# PLT-01-RevC.net
KiCad netlist of a schematic drawn in EAGLE
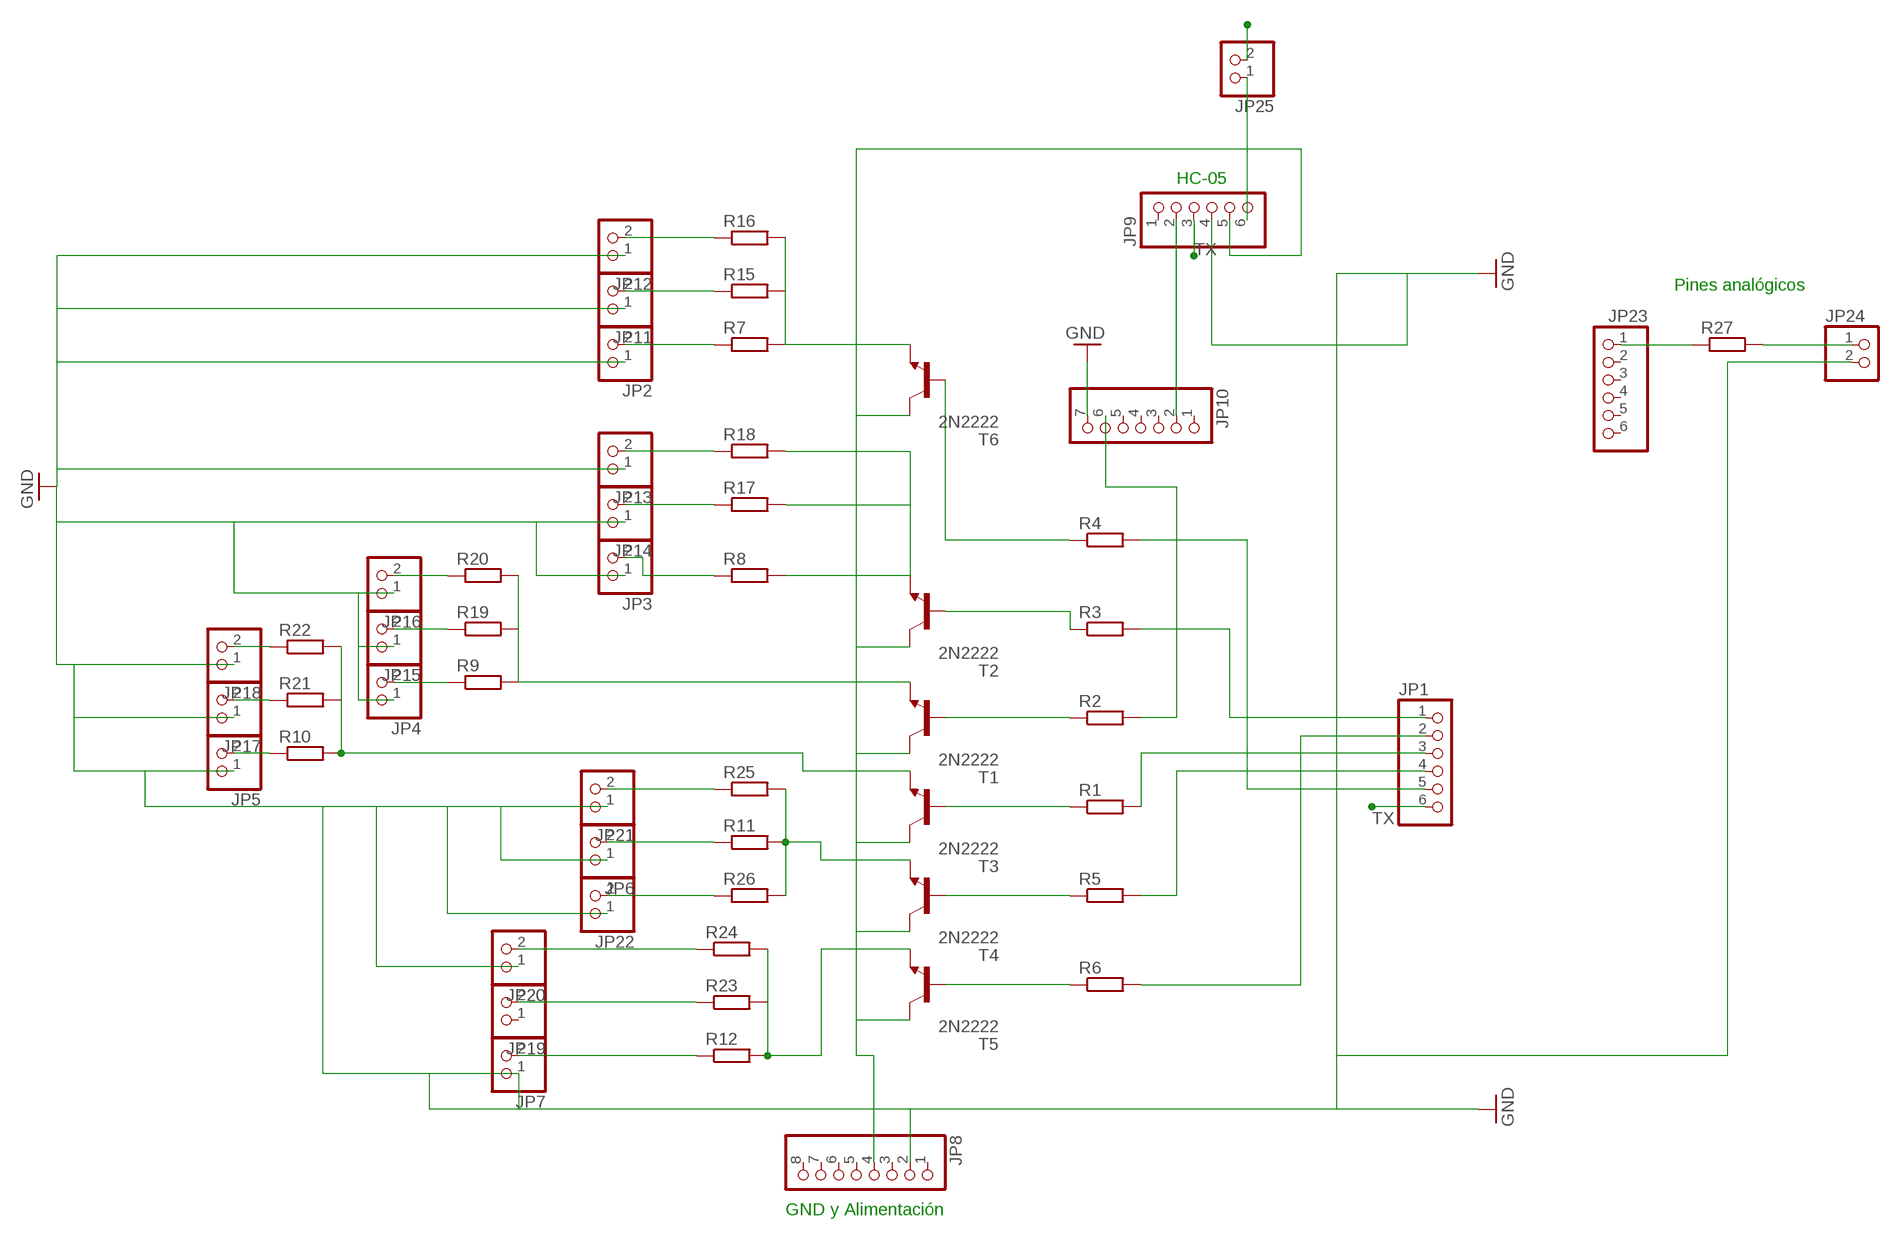
[diagram p0: schematic, sheet 1]

(export (version "E")
  (design (tool "Eeschema 10.0.6"))
  (components
    (comp (ref "JP1")
      (value "PINHD-1X6")
      (footprint "eagle-import:1X06")
      (libsource (lib "eagle-import") (part "PINHD-1X6"))
    )
    (comp (ref "JP2")
      (value "PINHD-1X2")
      (footprint "eagle-import:1X02")
      (libsource (lib "eagle-import") (part "PINHD-1X2"))
    )
    (comp (ref "JP3")
      (value "PINHD-1X2")
      (footprint "eagle-import:1X02")
      (libsource (lib "eagle-import") (part "PINHD-1X2"))
    )
    (comp (ref "JP4")
      (value "PINHD-1X2")
      (footprint "eagle-import:1X02")
      (libsource (lib "eagle-import") (part "PINHD-1X2"))
    )
    (comp (ref "JP5")
      (value "PINHD-1X2")
      (footprint "eagle-import:1X02")
      (libsource (lib "eagle-import") (part "PINHD-1X2"))
    )
    (comp (ref "JP6")
      (value "PINHD-1X2")
      (footprint "eagle-import:1X02")
      (libsource (lib "eagle-import") (part "PINHD-1X2"))
    )
    (comp (ref "JP7")
      (value "PINHD-1X2")
      (footprint "eagle-import:1X02")
      (libsource (lib "eagle-import") (part "PINHD-1X2"))
    )
    (comp (ref "JP8")
      (value "PINHD-1X8")
      (footprint "eagle-import:1X08")
      (libsource (lib "eagle-import") (part "PINHD-1X8"))
    )
    (comp (ref "JP9")
      (value "PINHD-1X6")
      (footprint "eagle-import:1X06")
      (libsource (lib "eagle-import") (part "PINHD-1X6"))
    )
    (comp (ref "JP10")
      (value "PINHD-1X7")
      (footprint "eagle-import:1X07")
      (libsource (lib "eagle-import") (part "PINHD-1X7"))
    )
    (comp (ref "JP11")
      (value "PINHD-1X2")
      (footprint "eagle-import:1X02")
      (libsource (lib "eagle-import") (part "PINHD-1X2"))
    )
    (comp (ref "JP12")
      (value "PINHD-1X2")
      (footprint "eagle-import:1X02")
      (libsource (lib "eagle-import") (part "PINHD-1X2"))
    )
    (comp (ref "JP13")
      (value "PINHD-1X2")
      (footprint "eagle-import:1X02")
      (libsource (lib "eagle-import") (part "PINHD-1X2"))
    )
    (comp (ref "JP14")
      (value "PINHD-1X2")
      (footprint "eagle-import:1X02")
      (libsource (lib "eagle-import") (part "PINHD-1X2"))
    )
    (comp (ref "JP15")
      (value "PINHD-1X2")
      (footprint "eagle-import:1X02")
      (libsource (lib "eagle-import") (part "PINHD-1X2"))
    )
    (comp (ref "JP16")
      (value "PINHD-1X2")
      (footprint "eagle-import:1X02")
      (libsource (lib "eagle-import") (part "PINHD-1X2"))
    )
    (comp (ref "JP17")
      (value "PINHD-1X2")
      (footprint "eagle-import:1X02")
      (libsource (lib "eagle-import") (part "PINHD-1X2"))
    )
    (comp (ref "JP18")
      (value "PINHD-1X2")
      (footprint "eagle-import:1X02")
      (libsource (lib "eagle-import") (part "PINHD-1X2"))
    )
    (comp (ref "JP19")
      (value "PINHD-1X2")
      (footprint "eagle-import:1X02")
      (libsource (lib "eagle-import") (part "PINHD-1X2"))
    )
    (comp (ref "JP20")
      (value "PINHD-1X2")
      (footprint "eagle-import:1X02")
      (libsource (lib "eagle-import") (part "PINHD-1X2"))
    )
    (comp (ref "JP21")
      (value "PINHD-1X2")
      (footprint "eagle-import:1X02")
      (libsource (lib "eagle-import") (part "PINHD-1X2"))
    )
    (comp (ref "JP22")
      (value "PINHD-1X2")
      (footprint "eagle-import:1X02")
      (libsource (lib "eagle-import") (part "PINHD-1X2"))
    )
    (comp (ref "JP23")
      (value "PINHD-1X6")
      (footprint "eagle-import:1X06")
      (libsource (lib "eagle-import") (part "PINHD-1X6"))
    )
    (comp (ref "JP24")
      (value "PINHD-1X2")
      (footprint "eagle-import:1X02")
      (libsource (lib "eagle-import") (part "PINHD-1X2"))
    )
    (comp (ref "JP25")
      (value "PINHD-1X2")
      (footprint "eagle-import:1X02")
      (libsource (lib "eagle-import") (part "PINHD-1X2"))
    )
    (comp (ref "R1")
      (value "R-EU_0207/10")
      (footprint "eagle-import:0207_10")
      (libsource (lib "eagle-import") (part "R-EU_0207/10"))
    )
    (comp (ref "R2")
      (value "R-EU_0207/10")
      (footprint "eagle-import:0207_10")
      (libsource (lib "eagle-import") (part "R-EU_0207/10"))
    )
    (comp (ref "R3")
      (value "R-EU_0207/10")
      (footprint "eagle-import:0207_10")
      (libsource (lib "eagle-import") (part "R-EU_0207/10"))
    )
    (comp (ref "R4")
      (value "R-EU_0207/10")
      (footprint "eagle-import:0207_10")
      (libsource (lib "eagle-import") (part "R-EU_0207/10"))
    )
    (comp (ref "R5")
      (value "R-EU_0207/10")
      (footprint "eagle-import:0207_10")
      (libsource (lib "eagle-import") (part "R-EU_0207/10"))
    )
    (comp (ref "R6")
      (value "R-EU_0207/10")
      (footprint "eagle-import:0207_10")
      (libsource (lib "eagle-import") (part "R-EU_0207/10"))
    )
    (comp (ref "R7")
      (value "R-EU_0207/10")
      (footprint "eagle-import:0207_10")
      (libsource (lib "eagle-import") (part "R-EU_0207/10"))
    )
    (comp (ref "R8")
      (value "R-EU_0207/10")
      (footprint "eagle-import:0207_10")
      (libsource (lib "eagle-import") (part "R-EU_0207/10"))
    )
    (comp (ref "R9")
      (value "R-EU_0207/10")
      (footprint "eagle-import:0207_10")
      (libsource (lib "eagle-import") (part "R-EU_0207/10"))
    )
    (comp (ref "R10")
      (value "R-EU_0207/10")
      (footprint "eagle-import:0207_10")
      (libsource (lib "eagle-import") (part "R-EU_0207/10"))
    )
    (comp (ref "R11")
      (value "R-EU_0207/10")
      (footprint "eagle-import:0207_10")
      (libsource (lib "eagle-import") (part "R-EU_0207/10"))
    )
    (comp (ref "R12")
      (value "R-EU_0207/10")
      (footprint "eagle-import:0207_10")
      (libsource (lib "eagle-import") (part "R-EU_0207/10"))
    )
    (comp (ref "R15")
      (value "R-EU_0207/10")
      (footprint "eagle-import:0207_10")
      (libsource (lib "eagle-import") (part "R-EU_0207/10"))
    )
    (comp (ref "R16")
      (value "R-EU_0207/10")
      (footprint "eagle-import:0207_10")
      (libsource (lib "eagle-import") (part "R-EU_0207/10"))
    )
    (comp (ref "R17")
      (value "R-EU_0207/10")
      (footprint "eagle-import:0207_10")
      (libsource (lib "eagle-import") (part "R-EU_0207/10"))
    )
    (comp (ref "R18")
      (value "R-EU_0207/10")
      (footprint "eagle-import:0207_10")
      (libsource (lib "eagle-import") (part "R-EU_0207/10"))
    )
    (comp (ref "R19")
      (value "R-EU_0207/10")
      (footprint "eagle-import:0207_10")
      (libsource (lib "eagle-import") (part "R-EU_0207/10"))
    )
    (comp (ref "R20")
      (value "R-EU_0207/10")
      (footprint "eagle-import:0207_10")
      (libsource (lib "eagle-import") (part "R-EU_0207/10"))
    )
    (comp (ref "R21")
      (value "R-EU_0207/10")
      (footprint "eagle-import:0207_10")
      (libsource (lib "eagle-import") (part "R-EU_0207/10"))
    )
    (comp (ref "R22")
      (value "R-EU_0207/10")
      (footprint "eagle-import:0207_10")
      (libsource (lib "eagle-import") (part "R-EU_0207/10"))
    )
    (comp (ref "R23")
      (value "R-EU_0207/10")
      (footprint "eagle-import:0207_10")
      (libsource (lib "eagle-import") (part "R-EU_0207/10"))
    )
    (comp (ref "R24")
      (value "R-EU_0207/10")
      (footprint "eagle-import:0207_10")
      (libsource (lib "eagle-import") (part "R-EU_0207/10"))
    )
    (comp (ref "R25")
      (value "R-EU_0207/10")
      (footprint "eagle-import:0207_10")
      (libsource (lib "eagle-import") (part "R-EU_0207/10"))
    )
    (comp (ref "R26")
      (value "R-EU_0207/10")
      (footprint "eagle-import:0207_10")
      (libsource (lib "eagle-import") (part "R-EU_0207/10"))
    )
    (comp (ref "R27")
      (value "R-EU_0207/10")
      (footprint "eagle-import:0207_10")
      (libsource (lib "eagle-import") (part "R-EU_0207/10"))
    )
    (comp (ref "T1")
      (value "2N2222")
      (footprint "eagle-import:TO92-EBC-OVAL")
      (libsource (lib "eagle-import") (part "2N2222"))
    )
    (comp (ref "T2")
      (value "2N2222")
      (footprint "eagle-import:TO92-EBC-OVAL")
      (libsource (lib "eagle-import") (part "2N2222"))
    )
    (comp (ref "T3")
      (value "2N2222")
      (footprint "eagle-import:TO92-EBC-OVAL")
      (libsource (lib "eagle-import") (part "2N2222"))
    )
    (comp (ref "T4")
      (value "2N2222")
      (footprint "eagle-import:TO92-EBC-OVAL")
      (libsource (lib "eagle-import") (part "2N2222"))
    )
    (comp (ref "T5")
      (value "2N2222")
      (footprint "eagle-import:TO92-EBC-OVAL")
      (libsource (lib "eagle-import") (part "2N2222"))
    )
    (comp (ref "T6")
      (value "2N2222")
      (footprint "eagle-import:TO92-EBC-OVAL")
      (libsource (lib "eagle-import") (part "2N2222"))
    )
  )
  (nets
    (net (code "1") (name "/5V") (class "Default")
      (node (ref "JP25") (pin "2") (pinfunction "2_2") (pintype "passive"))
      (node (ref "JP8") (pin "4") (pinfunction "4_4") (pintype "passive"))
      (node (ref "JP9") (pin "5") (pinfunction "5_5") (pintype "passive"))
      (node (ref "T1") (pin "C") (pinfunction "C_C") (pintype "passive"))
      (node (ref "T2") (pin "C") (pinfunction "C_C") (pintype "passive"))
      (node (ref "T3") (pin "C") (pinfunction "C_C") (pintype "passive"))
      (node (ref "T4") (pin "C") (pinfunction "C_C") (pintype "passive"))
      (node (ref "T5") (pin "C") (pinfunction "C_C") (pintype "passive"))
      (node (ref "T6") (pin "C") (pinfunction "C_C") (pintype "passive"))
    )
    (net (code "2") (name "/TX") (class "Default")
      (node (ref "JP1") (pin "6") (pinfunction "6_6") (pintype "passive"))
      (node (ref "JP9") (pin "3") (pinfunction "3_3") (pintype "passive"))
    )
    (net (code "3") (name "GND") (class "Default")
      (node (ref "JP10") (pin "7") (pinfunction "7_7") (pintype "passive"))
      (node (ref "JP11") (pin "1") (pinfunction "1_1") (pintype "passive"))
      (node (ref "JP12") (pin "1") (pinfunction "1_1") (pintype "passive"))
      (node (ref "JP13") (pin "1") (pinfunction "1_1") (pintype "passive"))
      (node (ref "JP14") (pin "1") (pinfunction "1_1") (pintype "passive"))
      (node (ref "JP15") (pin "1") (pinfunction "1_1") (pintype "passive"))
      (node (ref "JP16") (pin "1") (pinfunction "1_1") (pintype "passive"))
      (node (ref "JP17") (pin "1") (pinfunction "1_1") (pintype "passive"))
      (node (ref "JP18") (pin "1") (pinfunction "1_1") (pintype "passive"))
      (node (ref "JP2") (pin "1") (pinfunction "1_1") (pintype "passive"))
      (node (ref "JP20") (pin "1") (pinfunction "1_1") (pintype "passive"))
      (node (ref "JP21") (pin "1") (pinfunction "1_1") (pintype "passive"))
      (node (ref "JP22") (pin "1") (pinfunction "1_1") (pintype "passive"))
      (node (ref "JP24") (pin "2") (pinfunction "2_2") (pintype "passive"))
      (node (ref "JP3") (pin "1") (pinfunction "1_1") (pintype "passive"))
      (node (ref "JP4") (pin "1") (pinfunction "1_1") (pintype "passive"))
      (node (ref "JP5") (pin "1") (pinfunction "1_1") (pintype "passive"))
      (node (ref "JP6") (pin "1") (pinfunction "1_1") (pintype "passive"))
      (node (ref "JP7") (pin "1") (pinfunction "1_1") (pintype "passive"))
      (node (ref "JP8") (pin "2") (pinfunction "2_2") (pintype "passive"))
      (node (ref "JP9") (pin "4") (pinfunction "4_4") (pintype "passive"))
    )
    (net (code "4") (name "Net-(JP1-Pad1)") (class "Default")
      (node (ref "JP1") (pin "1") (pinfunction "1_1") (pintype "passive"))
      (node (ref "R3") (pin "2") (pinfunction "2_2") (pintype "passive"))
    )
    (net (code "5") (name "Net-(JP1-Pad2)") (class "Default")
      (node (ref "JP1") (pin "2") (pinfunction "2_2") (pintype "passive"))
      (node (ref "R6") (pin "2") (pinfunction "2_2") (pintype "passive"))
    )
    (net (code "6") (name "Net-(JP1-Pad3)") (class "Default")
      (node (ref "JP1") (pin "3") (pinfunction "3_3") (pintype "passive"))
      (node (ref "R1") (pin "2") (pinfunction "2_2") (pintype "passive"))
    )
    (net (code "7") (name "Net-(JP1-Pad4)") (class "Default")
      (node (ref "JP1") (pin "4") (pinfunction "4_4") (pintype "passive"))
      (node (ref "R5") (pin "2") (pinfunction "2_2") (pintype "passive"))
    )
    (net (code "8") (name "Net-(JP1-Pad5)") (class "Default")
      (node (ref "JP1") (pin "5") (pinfunction "5_5") (pintype "passive"))
      (node (ref "R4") (pin "2") (pinfunction "2_2") (pintype "passive"))
    )
    (net (code "9") (name "Net-(JP2-Pad2)") (class "Default")
      (node (ref "JP2") (pin "2") (pinfunction "2_2") (pintype "passive"))
      (node (ref "R7") (pin "1") (pinfunction "1_1") (pintype "passive"))
    )
    (net (code "10") (name "Net-(JP3-Pad2)") (class "Default")
      (node (ref "JP3") (pin "2") (pinfunction "2_2") (pintype "passive"))
      (node (ref "R8") (pin "1") (pinfunction "1_1") (pintype "passive"))
    )
    (net (code "11") (name "Net-(JP4-Pad2)") (class "Default")
      (node (ref "JP4") (pin "2") (pinfunction "2_2") (pintype "passive"))
      (node (ref "R9") (pin "1") (pinfunction "1_1") (pintype "passive"))
    )
    (net (code "12") (name "Net-(JP5-Pad2)") (class "Default")
      (node (ref "JP5") (pin "2") (pinfunction "2_2") (pintype "passive"))
      (node (ref "R10") (pin "1") (pinfunction "1_1") (pintype "passive"))
    )
    (net (code "13") (name "Net-(JP6-Pad2)") (class "Default")
      (node (ref "JP6") (pin "2") (pinfunction "2_2") (pintype "passive"))
      (node (ref "R11") (pin "1") (pinfunction "1_1") (pintype "passive"))
    )
    (net (code "14") (name "Net-(JP7-Pad2)") (class "Default")
      (node (ref "JP7") (pin "2") (pinfunction "2_2") (pintype "passive"))
      (node (ref "R12") (pin "1") (pinfunction "1_1") (pintype "passive"))
    )
    (net (code "15") (name "Net-(JP10-Pad2)") (class "Default")
      (node (ref "JP10") (pin "2") (pinfunction "2_2") (pintype "passive"))
      (node (ref "JP9") (pin "2") (pinfunction "2_2") (pintype "passive"))
    )
    (net (code "16") (name "Net-(JP10-Pad6)") (class "Default")
      (node (ref "JP10") (pin "6") (pinfunction "6_6") (pintype "passive"))
      (node (ref "R2") (pin "2") (pinfunction "2_2") (pintype "passive"))
    )
    (net (code "17") (name "Net-(JP11-Pad2)") (class "Default")
      (node (ref "JP11") (pin "2") (pinfunction "2_2") (pintype "passive"))
      (node (ref "R15") (pin "1") (pinfunction "1_1") (pintype "passive"))
    )
    (net (code "18") (name "Net-(JP12-Pad2)") (class "Default")
      (node (ref "JP12") (pin "2") (pinfunction "2_2") (pintype "passive"))
      (node (ref "R16") (pin "1") (pinfunction "1_1") (pintype "passive"))
    )
    (net (code "19") (name "Net-(JP13-Pad2)") (class "Default")
      (node (ref "JP13") (pin "2") (pinfunction "2_2") (pintype "passive"))
      (node (ref "R18") (pin "1") (pinfunction "1_1") (pintype "passive"))
    )
    (net (code "20") (name "Net-(JP14-Pad2)") (class "Default")
      (node (ref "JP14") (pin "2") (pinfunction "2_2") (pintype "passive"))
      (node (ref "R17") (pin "1") (pinfunction "1_1") (pintype "passive"))
    )
    (net (code "21") (name "Net-(JP15-Pad2)") (class "Default")
      (node (ref "JP15") (pin "2") (pinfunction "2_2") (pintype "passive"))
      (node (ref "R19") (pin "1") (pinfunction "1_1") (pintype "passive"))
    )
    (net (code "22") (name "Net-(JP16-Pad2)") (class "Default")
      (node (ref "JP16") (pin "2") (pinfunction "2_2") (pintype "passive"))
      (node (ref "R20") (pin "1") (pinfunction "1_1") (pintype "passive"))
    )
    (net (code "23") (name "Net-(JP17-Pad2)") (class "Default")
      (node (ref "JP17") (pin "2") (pinfunction "2_2") (pintype "passive"))
      (node (ref "R21") (pin "1") (pinfunction "1_1") (pintype "passive"))
    )
    (net (code "24") (name "Net-(JP18-Pad2)") (class "Default")
      (node (ref "JP18") (pin "2") (pinfunction "2_2") (pintype "passive"))
      (node (ref "R22") (pin "1") (pinfunction "1_1") (pintype "passive"))
    )
    (net (code "25") (name "Net-(JP19-Pad2)") (class "Default")
      (node (ref "JP19") (pin "2") (pinfunction "2_2") (pintype "passive"))
      (node (ref "R23") (pin "1") (pinfunction "1_1") (pintype "passive"))
    )
    (net (code "26") (name "Net-(JP20-Pad2)") (class "Default")
      (node (ref "JP20") (pin "2") (pinfunction "2_2") (pintype "passive"))
      (node (ref "R24") (pin "1") (pinfunction "1_1") (pintype "passive"))
    )
    (net (code "27") (name "Net-(JP21-Pad2)") (class "Default")
      (node (ref "JP21") (pin "2") (pinfunction "2_2") (pintype "passive"))
      (node (ref "R25") (pin "1") (pinfunction "1_1") (pintype "passive"))
    )
    (net (code "28") (name "Net-(JP22-Pad2)") (class "Default")
      (node (ref "JP22") (pin "2") (pinfunction "2_2") (pintype "passive"))
      (node (ref "R26") (pin "1") (pinfunction "1_1") (pintype "passive"))
    )
    (net (code "29") (name "Net-(JP23-Pad1)") (class "Default")
      (node (ref "JP23") (pin "1") (pinfunction "1_1") (pintype "passive"))
      (node (ref "R27") (pin "1") (pinfunction "1_1") (pintype "passive"))
    )
    (net (code "30") (name "Net-(JP24-Pad1)") (class "Default")
      (node (ref "JP24") (pin "1") (pinfunction "1_1") (pintype "passive"))
      (node (ref "R27") (pin "2") (pinfunction "2_2") (pintype "passive"))
    )
    (net (code "31") (name "Net-(JP25-Pad1)") (class "Default")
      (node (ref "JP25") (pin "1") (pinfunction "1_1") (pintype "passive"))
      (node (ref "JP9") (pin "6") (pinfunction "6_6") (pintype "passive"))
    )
    (net (code "32") (name "Net-(R1-Pad1)") (class "Default")
      (node (ref "R1") (pin "1") (pinfunction "1_1") (pintype "passive"))
      (node (ref "T3") (pin "B") (pinfunction "B_B") (pintype "passive"))
    )
    (net (code "33") (name "Net-(R2-Pad1)") (class "Default")
      (node (ref "R2") (pin "1") (pinfunction "1_1") (pintype "passive"))
      (node (ref "T1") (pin "B") (pinfunction "B_B") (pintype "passive"))
    )
    (net (code "34") (name "Net-(R3-Pad1)") (class "Default")
      (node (ref "R3") (pin "1") (pinfunction "1_1") (pintype "passive"))
      (node (ref "T2") (pin "B") (pinfunction "B_B") (pintype "passive"))
    )
    (net (code "35") (name "Net-(R4-Pad1)") (class "Default")
      (node (ref "R4") (pin "1") (pinfunction "1_1") (pintype "passive"))
      (node (ref "T6") (pin "B") (pinfunction "B_B") (pintype "passive"))
    )
    (net (code "36") (name "Net-(R5-Pad1)") (class "Default")
      (node (ref "R5") (pin "1") (pinfunction "1_1") (pintype "passive"))
      (node (ref "T4") (pin "B") (pinfunction "B_B") (pintype "passive"))
    )
    (net (code "37") (name "Net-(R6-Pad1)") (class "Default")
      (node (ref "R6") (pin "1") (pinfunction "1_1") (pintype "passive"))
      (node (ref "T5") (pin "B") (pinfunction "B_B") (pintype "passive"))
    )
    (net (code "38") (name "Net-(R10-Pad2)") (class "Default")
      (node (ref "R10") (pin "2") (pinfunction "2_2") (pintype "passive"))
      (node (ref "R21") (pin "2") (pinfunction "2_2") (pintype "passive"))
      (node (ref "R22") (pin "2") (pinfunction "2_2") (pintype "passive"))
      (node (ref "T3") (pin "E") (pinfunction "E_E") (pintype "passive"))
    )
    (net (code "39") (name "Net-(R11-Pad2)") (class "Default")
      (node (ref "R11") (pin "2") (pinfunction "2_2") (pintype "passive"))
      (node (ref "R25") (pin "2") (pinfunction "2_2") (pintype "passive"))
      (node (ref "R26") (pin "2") (pinfunction "2_2") (pintype "passive"))
      (node (ref "T4") (pin "E") (pinfunction "E_E") (pintype "passive"))
    )
    (net (code "40") (name "Net-(R12-Pad2)") (class "Default")
      (node (ref "R12") (pin "2") (pinfunction "2_2") (pintype "passive"))
      (node (ref "R23") (pin "2") (pinfunction "2_2") (pintype "passive"))
      (node (ref "R24") (pin "2") (pinfunction "2_2") (pintype "passive"))
      (node (ref "T5") (pin "E") (pinfunction "E_E") (pintype "passive"))
    )
    (net (code "41") (name "Net-(R15-Pad2)") (class "Default")
      (node (ref "R15") (pin "2") (pinfunction "2_2") (pintype "passive"))
      (node (ref "R16") (pin "2") (pinfunction "2_2") (pintype "passive"))
      (node (ref "R7") (pin "2") (pinfunction "2_2") (pintype "passive"))
      (node (ref "T6") (pin "E") (pinfunction "E_E") (pintype "passive"))
    )
    (net (code "42") (name "Net-(R17-Pad2)") (class "Default")
      (node (ref "R17") (pin "2") (pinfunction "2_2") (pintype "passive"))
      (node (ref "R18") (pin "2") (pinfunction "2_2") (pintype "passive"))
      (node (ref "R8") (pin "2") (pinfunction "2_2") (pintype "passive"))
      (node (ref "T2") (pin "E") (pinfunction "E_E") (pintype "passive"))
    )
    (net (code "43") (name "Net-(R19-Pad2)") (class "Default")
      (node (ref "R19") (pin "2") (pinfunction "2_2") (pintype "passive"))
      (node (ref "R20") (pin "2") (pinfunction "2_2") (pintype "passive"))
      (node (ref "R9") (pin "2") (pinfunction "2_2") (pintype "passive"))
      (node (ref "T1") (pin "E") (pinfunction "E_E") (pintype "passive"))
    )
    (net (code "44") (name "unconnected-(JP8-Pad1)") (class "Default")
      (node (ref "JP8") (pin "1") (pinfunction "1_1") (pintype "passive"))
    )
    (net (code "45") (name "unconnected-(JP8-Pad3)") (class "Default")
      (node (ref "JP8") (pin "3") (pinfunction "3_3") (pintype "passive"))
    )
    (net (code "46") (name "unconnected-(JP8-Pad5)") (class "Default")
      (node (ref "JP8") (pin "5") (pinfunction "5_5") (pintype "passive"))
    )
    (net (code "47") (name "unconnected-(JP8-Pad6)") (class "Default")
      (node (ref "JP8") (pin "6") (pinfunction "6_6") (pintype "passive"))
    )
    (net (code "48") (name "unconnected-(JP8-Pad7)") (class "Default")
      (node (ref "JP8") (pin "7") (pinfunction "7_7") (pintype "passive"))
    )
    (net (code "49") (name "unconnected-(JP8-Pad8)") (class "Default")
      (node (ref "JP8") (pin "8") (pinfunction "8_8") (pintype "passive"))
    )
    (net (code "50") (name "unconnected-(JP9-Pad1)") (class "Default")
      (node (ref "JP9") (pin "1") (pinfunction "1_1") (pintype "passive"))
    )
    (net (code "51") (name "unconnected-(JP10-Pad1)") (class "Default")
      (node (ref "JP10") (pin "1") (pinfunction "1_1") (pintype "passive"))
    )
    (net (code "52") (name "unconnected-(JP10-Pad3)") (class "Default")
      (node (ref "JP10") (pin "3") (pinfunction "3_3") (pintype "passive"))
    )
    (net (code "53") (name "unconnected-(JP10-Pad4)") (class "Default")
      (node (ref "JP10") (pin "4") (pinfunction "4_4") (pintype "passive"))
    )
    (net (code "54") (name "unconnected-(JP10-Pad5)") (class "Default")
      (node (ref "JP10") (pin "5") (pinfunction "5_5") (pintype "passive"))
    )
    (net (code "55") (name "unconnected-(JP19-Pad1)") (class "Default")
      (node (ref "JP19") (pin "1") (pinfunction "1_1") (pintype "passive"))
    )
    (net (code "56") (name "unconnected-(JP23-Pad2)") (class "Default")
      (node (ref "JP23") (pin "2") (pinfunction "2_2") (pintype "passive"))
    )
    (net (code "57") (name "unconnected-(JP23-Pad3)") (class "Default")
      (node (ref "JP23") (pin "3") (pinfunction "3_3") (pintype "passive"))
    )
    (net (code "58") (name "unconnected-(JP23-Pad4)") (class "Default")
      (node (ref "JP23") (pin "4") (pinfunction "4_4") (pintype "passive"))
    )
    (net (code "59") (name "unconnected-(JP23-Pad5)") (class "Default")
      (node (ref "JP23") (pin "5") (pinfunction "5_5") (pintype "passive"))
    )
    (net (code "60") (name "unconnected-(JP23-Pad6)") (class "Default")
      (node (ref "JP23") (pin "6") (pinfunction "6_6") (pintype "passive"))
    )
  )
)
